# AugmentedStethoscope_v5a.net
KiCad netlist of a schematic drawn in EAGLE
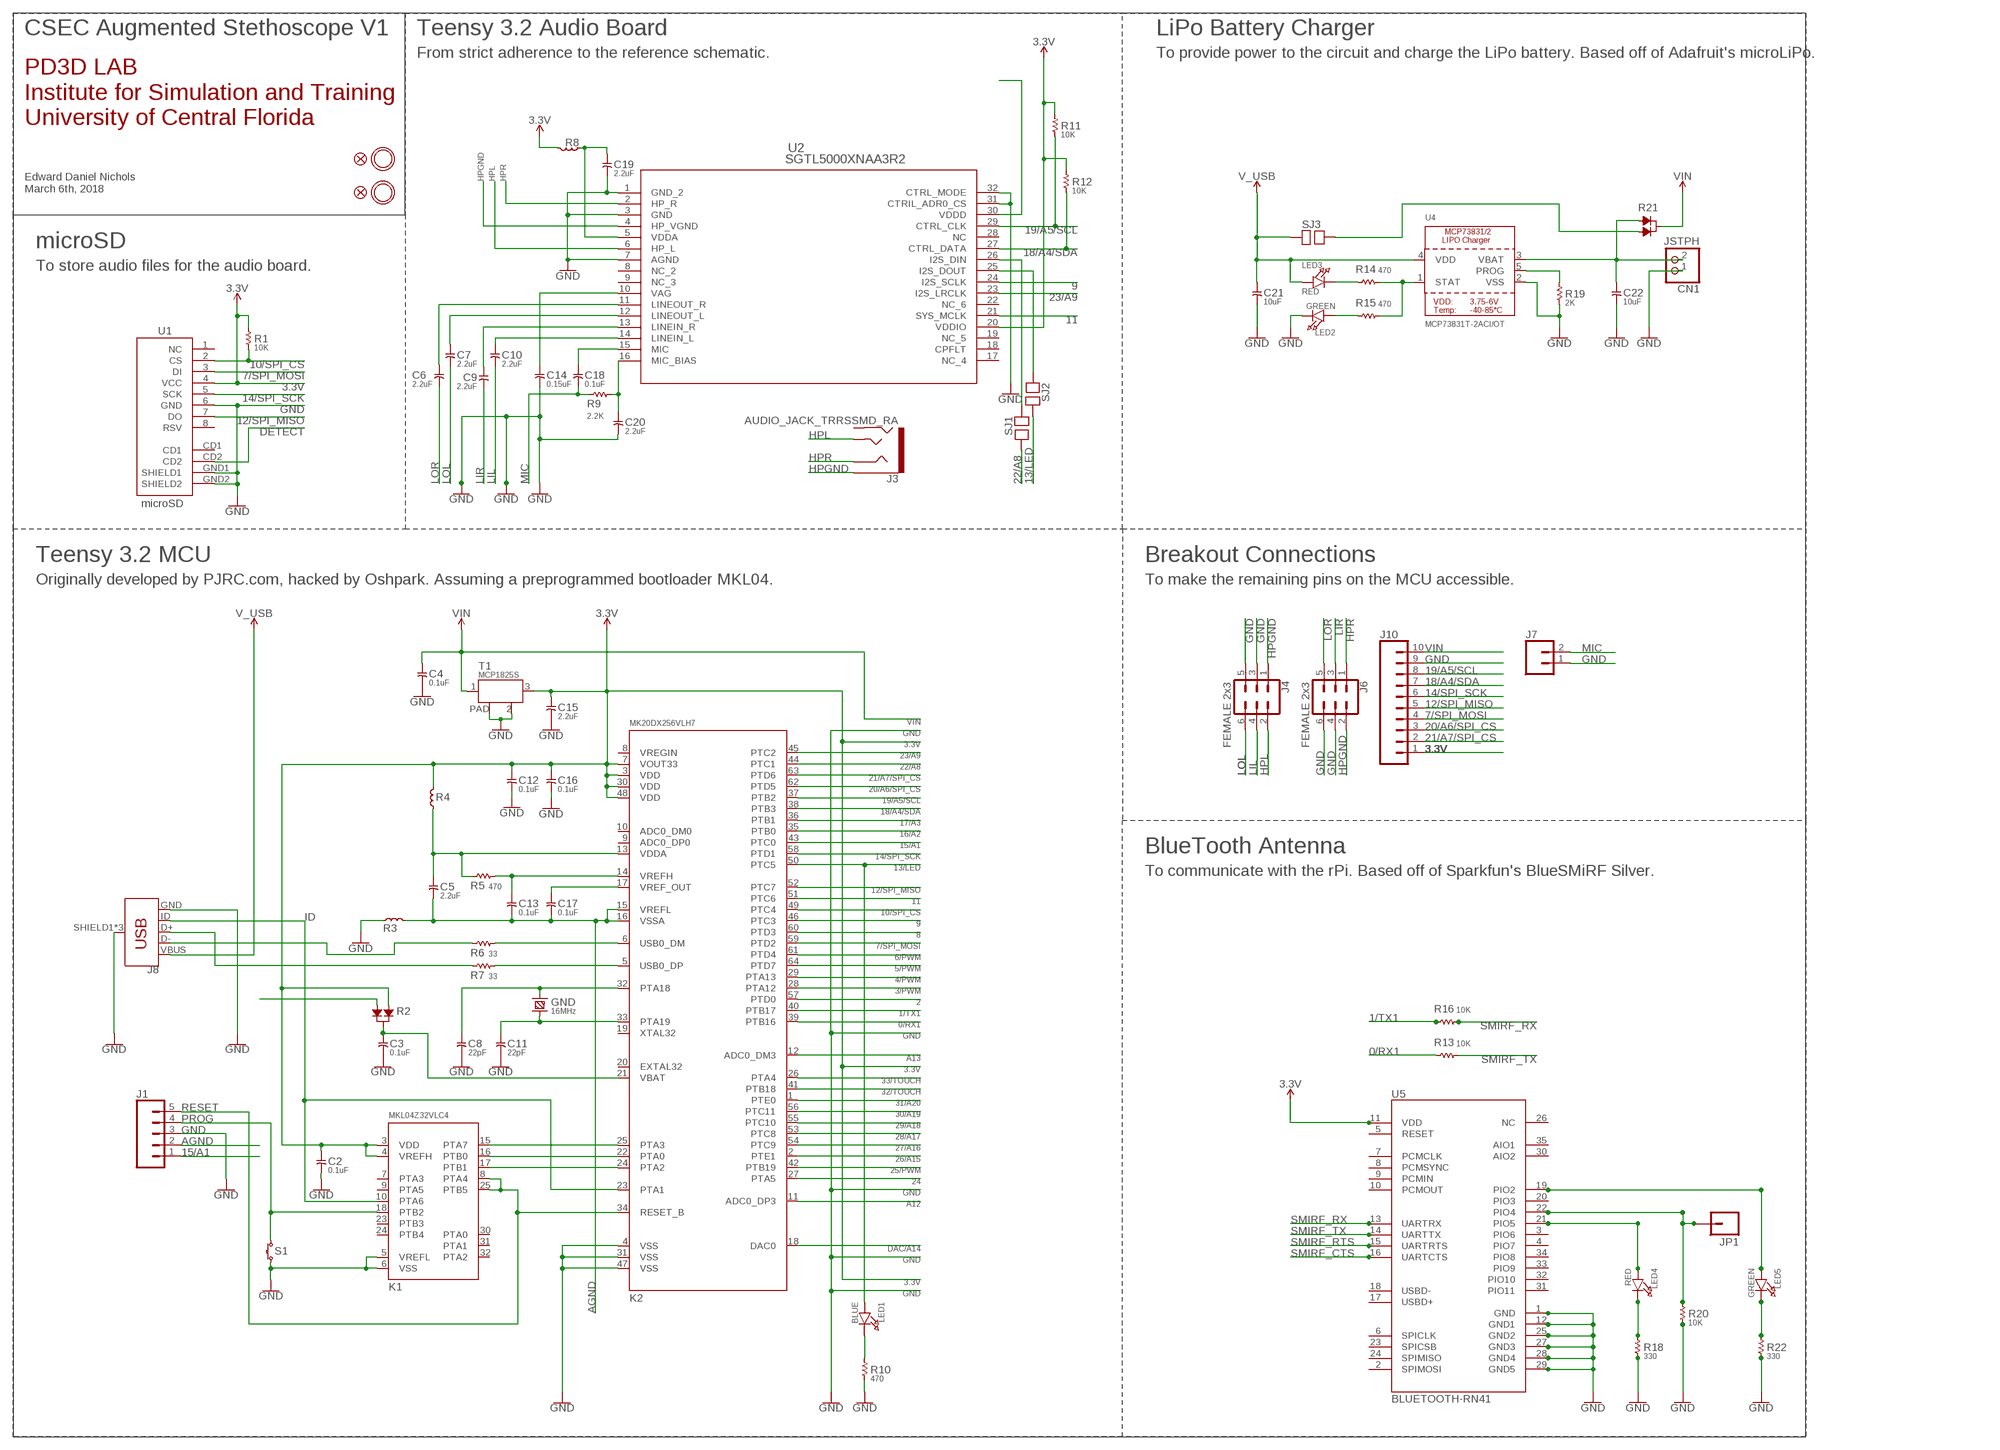
[diagram p0: schematic, sheet 1]

(export (version "E")
  (design (tool "Eeschema 10.0.6"))
  (components
    (comp (ref "C2")
      (value "0.1uF")
      (footprint "eagle-import:C0603")
      (fields (field (name "MF") "Murata Electronics") (field (name "MPN") "GRM188R71C104KA01D"))
      (libsource (lib "eagle-import") (part "CAPACITOR-0.1UF"))
    )
    (comp (ref "C3")
      (value "0.1uF")
      (footprint "eagle-import:C0603")
      (fields (field (name "MF") "Murata Electronics") (field (name "MPN") "GRM188R71C104KA01D"))
      (libsource (lib "eagle-import") (part "CAPACITOR-0.1UF"))
    )
    (comp (ref "C4")
      (value "0.1uF")
      (footprint "eagle-import:C0603")
      (fields (field (name "MF") "Murata Electronics") (field (name "MPN") "GRM188R71C104KA01D"))
      (libsource (lib "eagle-import") (part "CAPACITOR-0.1UF"))
    )
    (comp (ref "C5")
      (value "2.2uF")
      (footprint "eagle-import:C0805")
      (fields (field (name "MF") "Taiyo Yuden") (field (name "MPN") "TMK212B7225KG-TR"))
      (libsource (lib "eagle-import") (part "CAPACITOR-2.2UF"))
    )
    (comp (ref "C6")
      (value "2.2uF")
      (footprint "eagle-import:C0805")
      (fields (field (name "MF") "Taiyo Yuden") (field (name "MPN") "TMK212B7225KG-TR"))
      (libsource (lib "eagle-import") (part "CAPACITOR-2.2UF"))
    )
    (comp (ref "C7")
      (value "2.2uF")
      (footprint "eagle-import:C0805")
      (fields (field (name "MF") "Taiyo Yuden") (field (name "MPN") "TMK212B7225KG-TR"))
      (libsource (lib "eagle-import") (part "CAPACITOR-2.2UF"))
    )
    (comp (ref "C8")
      (value "22pF")
      (footprint "eagle-import:C0603")
      (fields (field (name "MF") "Vishay / Vitramon") (field (name "MPN") "VJ0603A220JXACW1BC"))
      (libsource (lib "eagle-import") (part "CAPACITOR-22PF"))
    )
    (comp (ref "C9")
      (value "2.2uF")
      (footprint "eagle-import:C0805")
      (fields (field (name "MF") "Taiyo Yuden") (field (name "MPN") "TMK212B7225KG-TR"))
      (libsource (lib "eagle-import") (part "CAPACITOR-2.2UF"))
    )
    (comp (ref "C10")
      (value "2.2uF")
      (footprint "eagle-import:C0805")
      (fields (field (name "MF") "Taiyo Yuden") (field (name "MPN") "TMK212B7225KG-TR"))
      (libsource (lib "eagle-import") (part "CAPACITOR-2.2UF"))
    )
    (comp (ref "C11")
      (value "22pF")
      (footprint "eagle-import:C0603")
      (fields (field (name "MF") "Vishay / Vitramon") (field (name "MPN") "VJ0603A220JXACW1BC"))
      (libsource (lib "eagle-import") (part "CAPACITOR-22PF"))
    )
    (comp (ref "C12")
      (value "0.1uF")
      (footprint "eagle-import:C0603")
      (fields (field (name "MF") "Murata Electronics") (field (name "MPN") "GRM188R71C104KA01D"))
      (libsource (lib "eagle-import") (part "CAPACITOR-0.1UF"))
    )
    (comp (ref "C13")
      (value "0.1uF")
      (footprint "eagle-import:C0603")
      (fields (field (name "MF") "Murata Electronics") (field (name "MPN") "GRM188R71C104KA01D"))
      (libsource (lib "eagle-import") (part "CAPACITOR-0.1UF"))
    )
    (comp (ref "C14")
      (value "0.15uF")
      (footprint "eagle-import:C0805")
      (fields (field (name "MF") "Taiyo Yuden") (field (name "MPN") "TMK212B7225KG-TR"))
      (libsource (lib "eagle-import") (part "CAPACITOR-2.2UF"))
    )
    (comp (ref "C15")
      (value "2.2uF")
      (footprint "eagle-import:C0805")
      (fields (field (name "MF") "Taiyo Yuden") (field (name "MPN") "TMK212B7225KG-TR"))
      (libsource (lib "eagle-import") (part "CAPACITOR-2.2UF"))
    )
    (comp (ref "C16")
      (value "0.1uF")
      (footprint "eagle-import:C0603")
      (fields (field (name "MF") "Murata Electronics") (field (name "MPN") "GRM188R71C104KA01D"))
      (libsource (lib "eagle-import") (part "CAPACITOR-0.1UF"))
    )
    (comp (ref "C17")
      (value "0.1uF")
      (footprint "eagle-import:C0603")
      (fields (field (name "MF") "Murata Electronics") (field (name "MPN") "GRM188R71C104KA01D"))
      (libsource (lib "eagle-import") (part "CAPACITOR-0.1UF"))
    )
    (comp (ref "C18")
      (value "0.1uF")
      (footprint "eagle-import:C0805")
      (fields (field (name "MF") "Taiyo Yuden") (field (name "MPN") "TMK212B7225KG-TR"))
      (libsource (lib "eagle-import") (part "CAPACITOR-2.2UF"))
    )
    (comp (ref "C19")
      (value "2.2uF")
      (footprint "eagle-import:C0805")
      (fields (field (name "MF") "Taiyo Yuden") (field (name "MPN") "TMK212B7225KG-TR"))
      (libsource (lib "eagle-import") (part "CAPACITOR-2.2UF"))
    )
    (comp (ref "C20")
      (value "2.2uF")
      (footprint "eagle-import:C0805")
      (fields (field (name "MF") "Taiyo Yuden") (field (name "MPN") "TMK212B7225KG-TR"))
      (libsource (lib "eagle-import") (part "CAPACITOR-2.2UF"))
    )
    (comp (ref "C21")
      (value "10uF")
      (footprint "eagle-import:C0603")
      (fields (field (name "MF") "Murata Electronics") (field (name "MPN") "GRM188R71C104KA01D"))
      (libsource (lib "eagle-import") (part "CAPACITOR-0.1UF"))
    )
    (comp (ref "C22")
      (value "10uF")
      (footprint "eagle-import:C0603")
      (fields (field (name "MF") "Murata Electronics") (field (name "MPN") "GRM188R71C104KA01D"))
      (libsource (lib "eagle-import") (part "CAPACITOR-0.1UF"))
    )
    (comp (ref "CN1")
      (value "JSTPH")
      (footprint "eagle-import:JSTPH2")
      (libsource (lib "eagle-import") (part "JST_2PIN"))
    )
    (comp (ref "FID2")
      (value "FIDUCIAL\"\"")
      (footprint "eagle-import:FIDUCIAL_1MM")
      (libsource (lib "eagle-import") (part "FIDUCIAL{dblquote}{dblquote}"))
    )
    (comp (ref "FID3")
      (value "FIDUCIAL\"\"")
      (footprint "eagle-import:FIDUCIAL_1MM")
      (fields (field (name "BOM") "EXCLUDE"))
      (libsource (lib "eagle-import") (part "FIDUCIAL{dblquote}{dblquote}"))
    )
    (comp (ref "GND")
      (value "16MHz")
      (footprint "eagle-import:HC49US")
      (fields (field (name "MF") "ABRACON") (field (name "MPN") "ABL-16.000MHz-B1U"))
      (libsource (lib "eagle-import") (part "CRYSTAL-HC49US"))
    )
    (comp (ref "J1")
      (value "CONN_05")
      (footprint "eagle-import:1X05")
      (libsource (lib "eagle-import") (part "CONN_05"))
    )
    (comp (ref "J3")
      (value "AUDIO_JACK_TRRSSMD_RA")
      (footprint "eagle-import:AUDIO_JACK_3.5MM_TRRS_SMD_RA")
      (libsource (lib "eagle-import") (part "AUDIO_JACK_TRRSSMD_RA"))
    )
    (comp (ref "J4")
      (value "FEMALE 2x3")
      (footprint "eagle-import:2X3")
      (libsource (lib "eagle-import") (part "CONN_03X2FEMALE"))
    )
    (comp (ref "J6")
      (value "FEMALE 2x3")
      (footprint "eagle-import:2X3")
      (libsource (lib "eagle-import") (part "CONN_03X2FEMALE"))
    )
    (comp (ref "J7")
      (value "CONN_02")
      (footprint "eagle-import:1X02")
      (libsource (lib "eagle-import") (part "CONN_02"))
    )
    (comp (ref "J8")
      (value "USB_MICRO-B_FEMALE-SMT")
      (footprint "eagle-import:USB-B-MICRO-SMD")
      (libsource (lib "eagle-import") (part "USB_MICRO-B_FEMALE-SMT"))
    )
    (comp (ref "J10")
      (value "CONN_10\"")
      (footprint "eagle-import:1X10")
      (libsource (lib "eagle-import") (part "CONN_10{dblquote}"))
    )
    (comp (ref "JP1")
      (value "M01SMDNS")
      (footprint "eagle-import:1X01NS")
      (libsource (lib "eagle-import") (part "M01SMDNS"))
    )
    (comp (ref "K1")
      (value "MKL04Z32VLC4")
      (footprint "eagle-import:LQFP32-08")
      (fields (field (name "MF") "PJRC") (field (name "MPN") "IC_MKL04Z32_TQFP32"))
      (libsource (lib "eagle-import") (part "MKL04Z32VLC4"))
    )
    (comp (ref "K2")
      (value "MK20DX256VLH7")
      (footprint "eagle-import:LQFP64-05")
      (fields (field (name "MF") "NXP"))
      (libsource (lib "eagle-import") (part "MK20DX256VLH7"))
    )
    (comp (ref "LED1")
      (value "BLUE")
      (footprint "eagle-import:CHIPLED_0805")
      (libsource (lib "eagle-import") (part "LED0805"))
    )
    (comp (ref "LED2")
      (value "GREEN")
      (footprint "eagle-import:CHIPLED_0805")
      (libsource (lib "eagle-import") (part "LED0805"))
    )
    (comp (ref "LED3")
      (value "RED")
      (footprint "eagle-import:CHIPLED_0805")
      (libsource (lib "eagle-import") (part "LED0805"))
    )
    (comp (ref "LED4")
      (value "RED")
      (footprint "eagle-import:CHIPLED_0805")
      (libsource (lib "eagle-import") (part "LED0805"))
    )
    (comp (ref "LED5")
      (value "GREEN")
      (footprint "eagle-import:CHIPLED_0805")
      (libsource (lib "eagle-import") (part "LED0805"))
    )
    (comp (ref "R1")
      (value "10K")
      (footprint "eagle-import:R0603")
      (fields (field (name "MF") "Vishay") (field (name "MPN") "CRCW0603470RFKEA"))
      (libsource (lib "eagle-import") (part "RESISTOR-470R"))
    )
    (comp (ref "R2")
      (value "DIODE_DUAL")
      (footprint "eagle-import:SOT-23")
      (fields (field (name "MF") "NXP Semiconductors") (field (name "MPN") "BAT54C,215"))
      (libsource (lib "eagle-import") (part "DIODE_DUAL"))
    )
    (comp (ref "R3")
      (value "FERRITE")
      (footprint "eagle-import:L0603")
      (fields (field (name "MF") "Murata Electronics") (field (name "MPN") " BLM18AG601SN1D"))
      (libsource (lib "eagle-import") (part "FERRITE"))
    )
    (comp (ref "R4")
      (value "FERRITE")
      (footprint "eagle-import:L0603")
      (fields (field (name "MF") "Murata Electronics") (field (name "MPN") " BLM18AG601SN1D"))
      (libsource (lib "eagle-import") (part "FERRITE"))
    )
    (comp (ref "R5")
      (value "470")
      (footprint "eagle-import:R0603")
      (fields (field (name "MF") "Vishay") (field (name "MPN") "CRCW0603470RFKEA"))
      (libsource (lib "eagle-import") (part "RESISTOR-470R"))
    )
    (comp (ref "R6")
      (value "33")
      (footprint "eagle-import:R0603")
      (fields (field (name "MF") "Panasonic") (field (name "MPN") "ERJ-PA3F33R0V"))
      (libsource (lib "eagle-import") (part "RESISTOR-33R"))
    )
    (comp (ref "R7")
      (value "33")
      (footprint "eagle-import:R0603")
      (fields (field (name "MF") "Panasonic") (field (name "MPN") "ERJ-PA3F33R0V"))
      (libsource (lib "eagle-import") (part "RESISTOR-33R"))
    )
    (comp (ref "R8")
      (value "FERRITE")
      (footprint "eagle-import:L0603")
      (fields (field (name "MF") "Murata Electronics") (field (name "MPN") " BLM18AG601SN1D"))
      (libsource (lib "eagle-import") (part "FERRITE"))
    )
    (comp (ref "R9")
      (value "2.2K")
      (footprint "eagle-import:R0603")
      (fields (field (name "MF") "Vishay") (field (name "MPN") "CRCW0603470RFKEA"))
      (libsource (lib "eagle-import") (part "RESISTOR-470R"))
    )
    (comp (ref "R10")
      (value "470")
      (footprint "eagle-import:R0603")
      (fields (field (name "MF") "Vishay") (field (name "MPN") "CRCW0603470RFKEA"))
      (libsource (lib "eagle-import") (part "RESISTOR-470R"))
    )
    (comp (ref "R11")
      (value "10K")
      (footprint "eagle-import:R0603")
      (fields (field (name "MF") "Vishay") (field (name "MPN") "CRCW0603470RFKEA"))
      (libsource (lib "eagle-import") (part "RESISTOR-470R"))
    )
    (comp (ref "R12")
      (value "10K")
      (footprint "eagle-import:R0603")
      (fields (field (name "MF") "Vishay") (field (name "MPN") "CRCW0603470RFKEA"))
      (libsource (lib "eagle-import") (part "RESISTOR-470R"))
    )
    (comp (ref "R13")
      (value "10K")
      (footprint "eagle-import:R0603")
      (fields (field (name "MF") "Panasonic") (field (name "MPN") "ERJ-PA3F33R0V"))
      (libsource (lib "eagle-import") (part "RESISTOR-33R"))
    )
    (comp (ref "R14")
      (value "470")
      (footprint "eagle-import:R0603")
      (fields (field (name "MF") "Panasonic") (field (name "MPN") "ERJ-PA3F33R0V"))
      (libsource (lib "eagle-import") (part "RESISTOR-33R"))
    )
    (comp (ref "R15")
      (value "470")
      (footprint "eagle-import:R0603")
      (fields (field (name "MF") "Panasonic") (field (name "MPN") "ERJ-PA3F33R0V"))
      (libsource (lib "eagle-import") (part "RESISTOR-33R"))
    )
    (comp (ref "R16")
      (value "10K")
      (footprint "eagle-import:R0603")
      (fields (field (name "MF") "Panasonic") (field (name "MPN") "ERJ-PA3F33R0V"))
      (libsource (lib "eagle-import") (part "RESISTOR-33R"))
    )
    (comp (ref "R18")
      (value "330")
      (footprint "eagle-import:R0603")
      (fields (field (name "MF") "Vishay") (field (name "MPN") "CRCW0603470RFKEA"))
      (libsource (lib "eagle-import") (part "RESISTOR-470R"))
    )
    (comp (ref "R19")
      (value "2K")
      (footprint "eagle-import:R0603")
      (fields (field (name "MF") "Vishay") (field (name "MPN") "CRCW0603470RFKEA"))
      (libsource (lib "eagle-import") (part "RESISTOR-470R"))
    )
    (comp (ref "R20")
      (value "10K")
      (footprint "eagle-import:R0603")
      (fields (field (name "MF") "Vishay") (field (name "MPN") "CRCW0603470RFKEA"))
      (libsource (lib "eagle-import") (part "RESISTOR-470R"))
    )
    (comp (ref "R21")
      (value "DIODE_DUAL")
      (footprint "eagle-import:SOT-23")
      (fields (field (name "MF") "NXP Semiconductors") (field (name "MPN") "BAT54C,215"))
      (libsource (lib "eagle-import") (part "DIODE_DUAL"))
    )
    (comp (ref "R22")
      (value "330")
      (footprint "eagle-import:R0603")
      (fields (field (name "MF") "Vishay") (field (name "MPN") "CRCW0603470RFKEA"))
      (libsource (lib "eagle-import") (part "RESISTOR-470R"))
    )
    (comp (ref "S1")
      (value "TACT_SWITCH")
      (footprint "eagle-import:ALPS_SKHH")
      (fields (field (name "MF") "ALPS") (field (name "MPN") "SKHHPKA010"))
      (libsource (lib "eagle-import") (part "TACT_SWITCH"))
    )
    (comp (ref "SJ1")
      (value "SOLDERJUMPER")
      (footprint "eagle-import:SOLDERJUMPER")
      (libsource (lib "eagle-import") (part "SOLDERJUMPER"))
    )
    (comp (ref "SJ2")
      (value "SOLDERJUMPER")
      (footprint "eagle-import:SOLDERJUMPER")
      (libsource (lib "eagle-import") (part "SOLDERJUMPER"))
    )
    (comp (ref "SJ3")
      (value "SOLDERJUMPER")
      (footprint "eagle-import:SOLDERJUMPER")
      (libsource (lib "eagle-import") (part "SOLDERJUMPER"))
    )
    (comp (ref "T1")
      (value "MCP1825S")
      (footprint "eagle-import:SOT-223")
      (fields (field (name "MF") "Microchip Technology") (field (name "MPN") "MCP1825S-3302E/DB"))
      (libsource (lib "eagle-import") (part "LDO"))
    )
    (comp (ref "U$1")
      (value "MOUNTINGHOLE2.5")
      (footprint "eagle-import:MOUNTINGHOLE_2.5_PLATED")
      (libsource (lib "eagle-import") (part "MOUNTINGHOLE2.5"))
    )
    (comp (ref "U$15")
      (value "MOUNTINGHOLE2.5")
      (footprint "eagle-import:MOUNTINGHOLE_2.5_PLATED")
      (libsource (lib "eagle-import") (part "MOUNTINGHOLE2.5"))
    )
    (comp (ref "U1")
      (value "microSD")
      (footprint "eagle-import:MICRO-SD-SOCKET-PP")
      (libsource (lib "eagle-import") (part "USD-SOCKETSMD"))
    )
    (comp (ref "U2")
      (value "SGTL5000XNAA3R2")
      (footprint "eagle-import:QFN32")
      (libsource (lib "eagle-import") (part "SGTL5000XNAA3R2"))
    )
    (comp (ref "U4")
      (value "MCP73831T-2ACI/OT")
      (footprint "eagle-import:SOT23-5")
      (libsource (lib "eagle-import") (part "MCP73831/2"))
    )
    (comp (ref "U5")
      (value "BLUETOOTH-RN41")
      (footprint "eagle-import:RN41")
      (libsource (lib "eagle-import") (part "BLUETOOTH-RN41{dblquote}"))
    )
  )
  (nets
    (net (code "1") (name "/0{slash}RX1") (class "Default")
      (node (ref "K2") (pin "39") (pinfunction "PTB16_39") (pintype "bidirectional"))
      (node (ref "R13") (pin "1") (pinfunction "1_1") (pintype "passive"))
    )
    (net (code "2") (name "/1{slash}TX1") (class "Default")
      (node (ref "K2") (pin "40") (pinfunction "PTB17_40") (pintype "bidirectional"))
      (node (ref "R16") (pin "1") (pinfunction "1_1") (pintype "passive"))
    )
    (net (code "3") (name "/2") (class "Default")
      (node (ref "K2") (pin "57") (pinfunction "PTD0_57") (pintype "bidirectional"))
    )
    (net (code "4") (name "/3{slash}PWM") (class "Default")
      (node (ref "K2") (pin "28") (pinfunction "PTA12_28") (pintype "bidirectional"))
    )
    (net (code "5") (name "/4{slash}PWM") (class "Default")
      (node (ref "K2") (pin "29") (pinfunction "PTA13_29") (pintype "bidirectional"))
    )
    (net (code "6") (name "/5{slash}PWM") (class "Default")
      (node (ref "K2") (pin "64") (pinfunction "PTD7_64") (pintype "bidirectional"))
    )
    (net (code "7") (name "/6{slash}PWM") (class "Default")
      (node (ref "K2") (pin "61") (pinfunction "PTD4_61") (pintype "bidirectional"))
    )
    (net (code "8") (name "/7{slash}SPI_MOSI") (class "Default")
      (node (ref "J10") (pin "4") (pinfunction "4_4") (pintype "passive"))
      (node (ref "K2") (pin "59") (pinfunction "PTD2_59") (pintype "bidirectional"))
      (node (ref "U1") (pin "3") (pinfunction "DI_3") (pintype "bidirectional"))
    )
    (net (code "9") (name "/8") (class "Default")
      (node (ref "K2") (pin "60") (pinfunction "PTD3_60") (pintype "bidirectional"))
    )
    (net (code "10") (name "/9") (class "Default")
      (node (ref "K2") (pin "46") (pinfunction "PTC3_46") (pintype "bidirectional"))
      (node (ref "U2") (pin "24") (pinfunction "I2S_SCLK_24") (pintype "passive"))
    )
    (net (code "11") (name "/10{slash}SPI_CS") (class "Default")
      (node (ref "K2") (pin "49") (pinfunction "PTC4_49") (pintype "bidirectional"))
      (node (ref "R1") (pin "1") (pinfunction "1_1") (pintype "passive"))
      (node (ref "U1") (pin "2") (pinfunction "CS_2") (pintype "bidirectional"))
    )
    (net (code "12") (name "/11") (class "Default")
      (node (ref "K2") (pin "51") (pinfunction "PTC6_51") (pintype "bidirectional"))
      (node (ref "U2") (pin "21") (pinfunction "SYS_MCLK_21") (pintype "passive"))
    )
    (net (code "13") (name "/12{slash}SPI_MISO") (class "Default")
      (node (ref "J10") (pin "5") (pinfunction "5_5") (pintype "passive"))
      (node (ref "K2") (pin "52") (pinfunction "PTC7_52") (pintype "bidirectional"))
      (node (ref "U1") (pin "7") (pinfunction "DO_7") (pintype "bidirectional"))
    )
    (net (code "14") (name "/13{slash}LED") (class "Default")
      (node (ref "K2") (pin "50") (pinfunction "PTC5_50") (pintype "bidirectional"))
      (node (ref "LED1") (pin "A") (pinfunction "A_A") (pintype "passive"))
      (node (ref "SJ2") (pin "2") (pinfunction "2_2") (pintype "passive"))
    )
    (net (code "15") (name "/14{slash}SPI_SCK") (class "Default")
      (node (ref "J10") (pin "6") (pinfunction "6_6") (pintype "passive"))
      (node (ref "K2") (pin "58") (pinfunction "PTD1_58") (pintype "bidirectional"))
      (node (ref "U1") (pin "5") (pinfunction "SCK_5") (pintype "bidirectional"))
    )
    (net (code "16") (name "/15{slash}A1") (class "Default")
      (node (ref "J1") (pin "1") (pinfunction "1_1") (pintype "passive"))
      (node (ref "K2") (pin "43") (pinfunction "PTC0_43") (pintype "bidirectional"))
    )
    (net (code "17") (name "/16{slash}A2") (class "Default")
      (node (ref "K2") (pin "35") (pinfunction "PTB0_35") (pintype "bidirectional"))
    )
    (net (code "18") (name "/17{slash}A3") (class "Default")
      (node (ref "K2") (pin "36") (pinfunction "PTB1_36") (pintype "bidirectional"))
    )
    (net (code "19") (name "/18{slash}A4{slash}SDA") (class "Default")
      (node (ref "J10") (pin "7") (pinfunction "7_7") (pintype "passive"))
      (node (ref "K2") (pin "38") (pinfunction "PTB3_38") (pintype "bidirectional"))
      (node (ref "R12") (pin "1") (pinfunction "1_1") (pintype "passive"))
      (node (ref "U2") (pin "27") (pinfunction "CTRL_DATA_27") (pintype "passive"))
    )
    (net (code "20") (name "/19{slash}A5{slash}SCL") (class "Default")
      (node (ref "J10") (pin "8") (pinfunction "8_8") (pintype "passive"))
      (node (ref "K2") (pin "37") (pinfunction "PTB2_37") (pintype "bidirectional"))
      (node (ref "R11") (pin "1") (pinfunction "1_1") (pintype "passive"))
      (node (ref "U2") (pin "29") (pinfunction "CTRL_CLK_29") (pintype "passive"))
    )
    (net (code "21") (name "/20{slash}A6{slash}SPI_CS") (class "Default")
      (node (ref "J10") (pin "3") (pinfunction "3_3") (pintype "passive"))
      (node (ref "K2") (pin "62") (pinfunction "PTD5_62") (pintype "bidirectional"))
    )
    (net (code "22") (name "/21{slash}A7{slash}SPI_CS") (class "Default")
      (node (ref "J10") (pin "2") (pinfunction "2_2") (pintype "passive"))
      (node (ref "K2") (pin "63") (pinfunction "PTD6_63") (pintype "bidirectional"))
    )
    (net (code "23") (name "/22{slash}A8") (class "Default")
      (node (ref "K2") (pin "44") (pinfunction "PTC1_44") (pintype "bidirectional"))
      (node (ref "SJ1") (pin "2") (pinfunction "2_2") (pintype "passive"))
    )
    (net (code "24") (name "/23{slash}A9") (class "Default")
      (node (ref "K2") (pin "45") (pinfunction "PTC2_45") (pintype "bidirectional"))
      (node (ref "U2") (pin "23") (pinfunction "I2S_LRCLK_23") (pintype "passive"))
    )
    (net (code "25") (name "/24") (class "Default")
      (node (ref "K2") (pin "27") (pinfunction "PTA5_27") (pintype "bidirectional"))
    )
    (net (code "26") (name "/25{slash}PWM") (class "Default")
      (node (ref "K2") (pin "42") (pinfunction "PTB19_42") (pintype "bidirectional"))
    )
    (net (code "27") (name "/26{slash}A15") (class "Default")
      (node (ref "K2") (pin "2") (pinfunction "PTE1_2") (pintype "bidirectional"))
    )
    (net (code "28") (name "/27{slash}A16") (class "Default")
      (node (ref "K2") (pin "54") (pinfunction "PTC9_54") (pintype "bidirectional"))
    )
    (net (code "29") (name "/28{slash}A17") (class "Default")
      (node (ref "K2") (pin "53") (pinfunction "PTC8_53") (pintype "bidirectional"))
    )
    (net (code "30") (name "/29{slash}A18") (class "Default")
      (node (ref "K2") (pin "55") (pinfunction "PTC10_55") (pintype "bidirectional"))
    )
    (net (code "31") (name "/30{slash}A19") (class "Default")
      (node (ref "K2") (pin "56") (pinfunction "PTC11_56") (pintype "bidirectional"))
    )
    (net (code "32") (name "/31{slash}A20") (class "Default")
      (node (ref "K2") (pin "1") (pinfunction "PTE0_1") (pintype "bidirectional"))
    )
    (net (code "33") (name "/32{slash}TOUCH") (class "Default")
      (node (ref "K2") (pin "41") (pinfunction "PTB18_41") (pintype "bidirectional"))
    )
    (net (code "34") (name "/33{slash}TOUCH") (class "Default")
      (node (ref "K2") (pin "26") (pinfunction "PTA4_26") (pintype "bidirectional"))
    )
    (net (code "35") (name "/A12") (class "Default")
      (node (ref "K2") (pin "11") (pinfunction "ADC0_DP3_11") (pintype "bidirectional"))
    )
    (net (code "36") (name "/A13") (class "Default")
      (node (ref "K2") (pin "12") (pinfunction "ADC0_DM3_12") (pintype "bidirectional"))
    )
    (net (code "37") (name "/AGND") (class "Default")
      (node (ref "C13") (pin "2") (pinfunction "2_2") (pintype "passive"))
      (node (ref "C17") (pin "2") (pinfunction "2_2") (pintype "passive"))
      (node (ref "C5") (pin "2") (pinfunction "2_2") (pintype "passive"))
      (node (ref "J1") (pin "2") (pinfunction "2_2") (pintype "passive"))
      (node (ref "K2") (pin "15") (pinfunction "VREFL_15") (pintype "bidirectional"))
      (node (ref "K2") (pin "16") (pinfunction "VSSA_16") (pintype "bidirectional"))
      (node (ref "R3") (pin "2") (pinfunction "2_2") (pintype "passive"))
    )
    (net (code "38") (name "/DAC{slash}A14") (class "Default")
      (node (ref "K2") (pin "18") (pinfunction "DAC0_18") (pintype "bidirectional"))
    )
    (net (code "39") (name "/DETECT") (class "Default")
      (node (ref "U1") (pin "CD2") (pinfunction "CD2_CD2") (pintype "bidirectional"))
    )
    (net (code "40") (name "/HPGND") (class "Default")
      (node (ref "J3") (pin "EARTH") (pinfunction "EARTH_EARTH") (pintype "bidirectional"))
      (node (ref "J4") (pin "1") (pinfunction "1_1") (pintype "bidirectional"))
      (node (ref "J6") (pin "2") (pinfunction "2_2") (pintype "bidirectional"))
      (node (ref "U2") (pin "4") (pinfunction "HP_VGND_4") (pintype "power_in"))
    )
    (net (code "41") (name "/HPL") (class "Default")
      (node (ref "J3") (pin "TIP") (pinfunction "TIP_TIP") (pintype "bidirectional"))
      (node (ref "J4") (pin "2") (pinfunction "2_2") (pintype "bidirectional"))
      (node (ref "U2") (pin "6") (pinfunction "HP_L_6") (pintype "output"))
    )
    (net (code "42") (name "/HPR") (class "Default")
      (node (ref "J3") (pin "RING1") (pinfunction "RING1_RING1") (pintype "bidirectional"))
      (node (ref "J6") (pin "1") (pinfunction "1_1") (pintype "bidirectional"))
      (node (ref "U2") (pin "2") (pinfunction "HP_R_2") (pintype "output"))
    )
    (net (code "43") (name "/ID") (class "Default")
      (node (ref "J8") (pin "ID") (pinfunction "ID_ID") (pintype "bidirectional"))
      (node (ref "K1") (pin "10") (pinfunction "PTA6_10") (pintype "bidirectional"))
      (node (ref "K2") (pin "23") (pinfunction "PTA1_23") (pintype "bidirectional"))
    )
    (net (code "44") (name "/LIL") (class "Default")
      (node (ref "C10") (pin "2") (pinfunction "2_2") (pintype "passive"))
      (node (ref "J4") (pin "4") (pinfunction "4_4") (pintype "bidirectional"))
    )
    (net (code "45") (name "/LIR") (class "Default")
      (node (ref "C9") (pin "2") (pinfunction "2_2") (pintype "passive"))
      (node (ref "J6") (pin "3") (pinfunction "3_3") (pintype "bidirectional"))
    )
    (net (code "46") (name "/LOL") (class "Default")
      (node (ref "C7") (pin "2") (pinfunction "2_2") (pintype "passive"))
      (node (ref "J4") (pin "6") (pinfunction "6_6") (pintype "bidirectional"))
    )
    (net (code "47") (name "/LOR") (class "Default")
      (node (ref "C6") (pin "2") (pinfunction "2_2") (pintype "passive"))
      (node (ref "J6") (pin "5") (pinfunction "5_5") (pintype "bidirectional"))
    )
    (net (code "48") (name "/MIC") (class "Default")
      (node (ref "C18") (pin "2") (pinfunction "2_2") (pintype "passive"))
      (node (ref "J7") (pin "2") (pinfunction "2_2") (pintype "passive"))
      (node (ref "R9") (pin "1") (pinfunction "1_1") (pintype "passive"))
    )
    (net (code "49") (name "/PROG") (class "Default")
      (node (ref "J1") (pin "4") (pinfunction "4_4") (pintype "passive"))
      (node (ref "K1") (pin "18") (pinfunction "PTB2_18") (pintype "bidirectional"))
      (node (ref "S1") (pin "1") (pinfunction "1_1") (pintype "passive"))
      (node (ref "S1") (pin "2") (pinfunction "1_2") (pintype "passive"))
    )
    (net (code "50") (name "/RESET") (class "Default")
      (node (ref "J1") (pin "5") (pinfunction "5_5") (pintype "passive"))
      (node (ref "K1") (pin "25") (pinfunction "PTB5_25") (pintype "bidirectional"))
      (node (ref "K1") (pin "8") (pinfunction "PTA4_8") (pintype "bidirectional"))
      (node (ref "K2") (pin "34") (pinfunction "RESET_B_34") (pintype "bidirectional"))
    )
    (net (code "51") (name "/SMIRF_CTS") (class "Default")
      (node (ref "U5") (pin "16") (pinfunction "UARTCTS_16") (pintype "bidirectional"))
    )
    (net (code "52") (name "/SMIRF_RTS") (class "Default")
      (node (ref "U5") (pin "15") (pinfunction "UARTRTS_15") (pintype "bidirectional"))
    )
    (net (code "53") (name "/SMIRF_RX") (class "Default")
      (node (ref "R16") (pin "2") (pinfunction "2_2") (pintype "passive"))
      (node (ref "U5") (pin "13") (pinfunction "UARTRX_13") (pintype "bidirectional"))
    )
    (net (code "54") (name "/SMIRF_TX") (class "Default")
      (node (ref "R13") (pin "2") (pinfunction "2_2") (pintype "passive"))
      (node (ref "U5") (pin "14") (pinfunction "UARTTX_14") (pintype "bidirectional"))
    )
    (net (code "55") (name "3.3V") (class "Default")
      (node (ref "C12") (pin "1") (pinfunction "1_1") (pintype "passive"))
      (node (ref "C15") (pin "1") (pinfunction "1_1") (pintype "passive"))
      (node (ref "C16") (pin "1") (pinfunction "1_1") (pintype "passive"))
      (node (ref "C2") (pin "1") (pinfunction "1_1") (pintype "passive"))
      (node (ref "J10") (pin "1") (pinfunction "1_1") (pintype "passive"))
      (node (ref "K1") (pin "3") (pinfunction "VDD_3") (pintype "bidirectional"))
      (node (ref "K1") (pin "4") (pinfunction "VREFH_4") (pintype "bidirectional"))
      (node (ref "K2") (pin "3") (pinfunction "VDD_3") (pintype "bidirectional"))
      (node (ref "K2") (pin "30") (pinfunction "VDD_30") (pintype "bidirectional"))
      (node (ref "K2") (pin "48") (pinfunction "VDD_48") (pintype "bidirectional"))
      (node (ref "K2") (pin "7") (pinfunction "VOUT33_7") (pintype "bidirectional"))
      (node (ref "R1") (pin "2") (pinfunction "2_2") (pintype "passive"))
      (node (ref "R11") (pin "2") (pinfunction "2_2") (pintype "passive"))
      (node (ref "R12") (pin "2") (pinfunction "2_2") (pintype "passive"))
      (node (ref "R2") (pin "1") (pinfunction "1_1") (pintype "bidirectional"))
      (node (ref "R4") (pin "2") (pinfunction "2_2") (pintype "passive"))
      (node (ref "R8") (pin "2") (pinfunction "2_2") (pintype "passive"))
      (node (ref "T1") (pin "3") (pinfunction "OUT_3") (pintype "bidirectional"))
      (node (ref "U1") (pin "4") (pinfunction "VCC_4") (pintype "bidirectional"))
      (node (ref "U2") (pin "20") (pinfunction "VDDIO_20") (pintype "power_in"))
      (node (ref "U5") (pin "11") (pinfunction "VDD_11") (pintype "bidirectional"))
    )
    (net (code "56") (name "GND") (class "Default")
      (node (ref "C11") (pin "2") (pinfunction "2_2") (pintype "passive"))
      (node (ref "C12") (pin "2") (pinfunction "2_2") (pintype "passive"))
      (node (ref "C14") (pin "2") (pinfunction "2_2") (pintype "passive"))
      (node (ref "C15") (pin "2") (pinfunction "2_2") (pintype "passive"))
      (node (ref "C16") (pin "2") (pinfunction "2_2") (pintype "passive"))
      (node (ref "C19") (pin "2") (pinfunction "2_2") (pintype "passive"))
      (node (ref "C2") (pin "2") (pinfunction "2_2") (pintype "passive"))
      (node (ref "C20") (pin "2") (pinfunction "2_2") (pintype "passive"))
      (node (ref "C21") (pin "2") (pinfunction "2_2") (pintype "passive"))
      (node (ref "C22") (pin "2") (pinfunction "2_2") (pintype "passive"))
      (node (ref "C3") (pin "2") (pinfunction "2_2") (pintype "passive"))
      (node (ref "C4") (pin "2") (pinfunction "2_2") (pintype "passive"))
      (node (ref "C8") (pin "2") (pinfunction "2_2") (pintype "passive"))
      (node (ref "CN1") (pin "1") (pinfunction "1_1") (pintype "passive"))
      (node (ref "J1") (pin "3") (pinfunction "3_3") (pintype "passive"))
      (node (ref "J10") (pin "9") (pinfunction "9_9") (pintype "passive"))
      (node (ref "J4") (pin "3") (pinfunction "3_3") (pintype "bidirectional"))
      (node (ref "J4") (pin "5") (pinfunction "5_5") (pintype "bidirectional"))
      (node (ref "J6") (pin "4") (pinfunction "4_4") (pintype "bidirectional"))
      (node (ref "J6") (pin "6") (pinfunction "6_6") (pintype "bidirectional"))
      (node (ref "J7") (pin "1") (pinfunction "1_1") (pintype "passive"))
      (node (ref "J8") (pin "GND") (pinfunction "GND_GND") (pintype "power_in"))
      (node (ref "J8") (pin "SHIELD1") (pinfunction "SHIELD_SHIELD1") (pintype "bidirectional"))
      (node (ref "J8") (pin "SHIELD2") (pinfunction "SHIELD_SHIELD2") (pintype "bidirectional"))
      (node (ref "J8") (pin "SHIELD3") (pinfunction "SHIELD_SHIELD3") (pintype "bidirectional"))
      (node (ref "K1") (pin "5") (pinfunction "VREFL_5") (pintype "bidirectional"))
      (node (ref "K1") (pin "6") (pinfunction "VSS_6") (pintype "bidirectional"))
      (node (ref "K2") (pin "31") (pinfunction "VSS_31") (pintype "bidirectional"))
      (node (ref "K2") (pin "4") (pinfunction "VSS_4") (pintype "bidirectional"))
      (node (ref "K2") (pin "47") (pinfunction "VSS_47") (pintype "bidirectional"))
      (node (ref "LED2") (pin "C") (pinfunction "C_C") (pintype "passive"))
      (node (ref "R10") (pin "1") (pinfunction "1_1") (pintype "passive"))
      (node (ref "R18") (pin "1") (pinfunction "1_1") (pintype "passive"))
      (node (ref "R19") (pin "1") (pinfunction "1_1") (pintype "passive"))
      (node (ref "R20") (pin "1") (pinfunction "1_1") (pintype "passive"))
      (node (ref "R22") (pin "1") (pinfunction "1_1") (pintype "passive"))
      (node (ref "R3") (pin "1") (pinfunction "1_1") (pintype "passive"))
      (node (ref "S1") (pin "3") (pinfunction "3_3") (pintype "passive"))
      (node (ref "S1") (pin "4") (pinfunction "3_4") (pintype "passive"))
      (node (ref "T1") (pin "2") (pinfunction "GND_2") (pintype "bidirectional"))
      (node (ref "T1") (pin "PAD") (pinfunction "PAD_PAD") (pintype "bidirectional"))
      (node (ref "U1") (pin "6") (pinfunction "GND_6") (pintype "bidirectional"))
      (node (ref "U1") (pin "GND1") (pinfunction "SHIELD1_GND1") (pintype "bidirectional"))
      (node (ref "U1") (pin "GND2") (pinfunction "SHIELD2_GND2") (pintype "bidirectional"))
      (node (ref "U2") (pin "1") (pinfunction "GND_2_1") (pintype "power_in"))
      (node (ref "U2") (pin "3") (pinfunction "GND_3") (pintype "power_in"))
      (node (ref "U2") (pin "31") (pinfunction "CTRIL_ADR0_CS_31") (pintype "passive"))
      (node (ref "U2") (pin "32") (pinfunction "CTRL_MODE_32") (pintype "passive"))
      (node (ref "U2") (pin "7") (pinfunction "AGND_7") (pintype "power_in"))
      (node (ref "U4") (pin "2") (pinfunction "VSS_2") (pintype "power_in"))
      (node (ref "U5") (pin "1") (pinfunction "GND_1") (pintype "bidirectional"))
      (node (ref "U5") (pin "12") (pinfunction "GND1_12") (pintype "bidirectional"))
      (node (ref "U5") (pin "25") (pinfunction "GND2_25") (pintype "bidirectional"))
      (node (ref "U5") (pin "27") (pinfunction "GND3_27") (pintype "bidirectional"))
      (node (ref "U5") (pin "28") (pinfunction "GND4_28") (pintype "bidirectional"))
      (node (ref "U5") (pin "29") (pinfunction "GND5_29") (pintype "bidirectional"))
    )
    (net (code "57") (name "Net-(J8-PadD+)") (class "Default")
      (node (ref "J8") (pin "D+") (pinfunction "D+_D+") (pintype "bidirectional"))
      (node (ref "R7") (pin "1") (pinfunction "1_1") (pintype "passive"))
    )
    (net (code "58") (name "Net-(J8-PadD-)") (class "Default")
      (node (ref "J8") (pin "D-") (pinfunction "D-_D-") (pintype "bidirectional"))
      (node (ref "R6") (pin "1") (pinfunction "1_1") (pintype "passive"))
    )
    (net (code "59") (name "Net-(K1-PTA7)") (class "Default")
      (node (ref "K1") (pin "15") (pinfunction "PTA7_15") (pintype "bidirectional"))
      (node (ref "K2") (pin "25") (pinfunction "PTA3_25") (pintype "bidirectional"))
    )
    (net (code "60") (name "Net-(K1-PTB0)") (class "Default")
      (node (ref "K1") (pin "16") (pinfunction "PTB0_16") (pintype "bidirectional"))
      (node (ref "K2") (pin "22") (pinfunction "PTA0_22") (pintype "bidirectional"))
    )
    (net (code "61") (name "Net-(K1-PTB1)") (class "Default")
      (node (ref "K1") (pin "17") (pinfunction "PTB1_17") (pintype "bidirectional"))
      (node (ref "K2") (pin "24") (pinfunction "PTA2_24") (pintype "bidirectional"))
    )
    (net (code "62") (name "Net-(K2-PTA18)") (class "Default")
      (node (ref "C8") (pin "1") (pinfunction "1_1") (pintype "passive"))
      (node (ref "GND") (pin "1") (pinfunction "1_1") (pintype "passive"))
      (node (ref "K2") (pin "32") (pinfunction "PTA18_32") (pintype "bidirectional"))
    )
    (net (code "63") (name "Net-(K2-PTA19)") (class "Default")
      (node (ref "C11") (pin "1") (pinfunction "1_1") (pintype "passive"))
      (node (ref "GND") (pin "2") (pinfunction "2_2") (pintype "passive"))
      (node (ref "K2") (pin "33") (pinfunction "PTA19_33") (pintype "bidirectional"))
    )
    (net (code "64") (name "Net-(K2-USB0_DM)") (class "Default")
      (node (ref "K2") (pin "6") (pinfunction "USB0_DM_6") (pintype "bidirectional"))
      (node (ref "R6") (pin "2") (pinfunction "2_2") (pintype "passive"))
    )
    (net (code "65") (name "Net-(K2-USB0_DP)") (class "Default")
      (node (ref "K2") (pin "5") (pinfunction "USB0_DP_5") (pintype "bidirectional"))
      (node (ref "R7") (pin "2") (pinfunction "2_2") (pintype "passive"))
    )
    (net (code "66") (name "Net-(K2-VBAT)") (class "Default")
      (node (ref "C3") (pin "1") (pinfunction "1_1") (pintype "passive"))
      (node (ref "K2") (pin "21") (pinfunction "VBAT_21") (pintype "bidirectional"))
      (node (ref "R2") (pin "3") (pinfunction "3_3") (pintype "bidirectional"))
    )
    (net (code "67") (name "Net-(K2-VDDA)") (class "Default")
      (node (ref "C5") (pin "1") (pinfunction "1_1") (pintype "passive"))
      (node (ref "K2") (pin "13") (pinfunction "VDDA_13") (pintype "bidirectional"))
      (node (ref "R4") (pin "1") (pinfunction "1_1") (pintype "passive"))
      (node (ref "R5") (pin "1") (pinfunction "1_1") (pintype "passive"))
    )
    (net (code "68") (name "Net-(K2-VREFH)") (class "Default")
      (node (ref "C13") (pin "1") (pinfunction "1_1") (pintype "passive"))
      (node (ref "K2") (pin "14") (pinfunction "VREFH_14") (pintype "bidirectional"))
      (node (ref "R5") (pin "2") (pinfunction "2_2") (pintype "passive"))
    )
    (net (code "69") (name "Net-(K2-VREF_OUT)") (class "Default")
      (node (ref "C17") (pin "1") (pinfunction "1_1") (pintype "passive"))
      (node (ref "K2") (pin "17") (pinfunction "VREF_OUT_17") (pintype "bidirectional"))
    )
    (net (code "70") (name "Net-(LED1-PadC)") (class "Default")
      (node (ref "LED1") (pin "C") (pinfunction "C_C") (pintype "passive"))
      (node (ref "R10") (pin "2") (pinfunction "2_2") (pintype "passive"))
    )
    (net (code "71") (name "Net-(LED2-PadA)") (class "Default")
      (node (ref "LED2") (pin "A") (pinfunction "A_A") (pintype "passive"))
      (node (ref "R15") (pin "1") (pinfunction "1_1") (pintype "passive"))
    )
    (net (code "72") (name "Net-(LED3-PadC)") (class "Default")
      (node (ref "LED3") (pin "C") (pinfunction "C_C") (pintype "passive"))
      (node (ref "R14") (pin "1") (pinfunction "1_1") (pintype "passive"))
    )
    (net (code "73") (name "Net-(LED4-PadC)") (class "Default")
      (node (ref "LED4") (pin "C") (pinfunction "C_C") (pintype "passive"))
      (node (ref "R18") (pin "2") (pinfunction "2_2") (pintype "passive"))
    )
    (net (code "74") (name "Net-(LED5-PadC)") (class "Default")
      (node (ref "LED5") (pin "C") (pinfunction "C_C") (pintype "passive"))
      (node (ref "R22") (pin "2") (pinfunction "2_2") (pintype "passive"))
    )
    (net (code "75") (name "Net-(R21-Pad2)") (class "Default")
      (node (ref "R21") (pin "2") (pinfunction "2_2") (pintype "bidirectional"))
      (node (ref "SJ3") (pin "2") (pinfunction "2_2") (pintype "passive"))
    )
    (net (code "76") (name "Net-(U2-I2S_DIN)") (class "Default")
      (node (ref "SJ1") (pin "1") (pinfunction "1_1") (pintype "passive"))
      (node (ref "U2") (pin "26") (pinfunction "I2S_DIN_26") (pintype "input"))
    )
    (net (code "77") (name "Net-(U2-I2S_DOUT)") (class "Default")
      (node (ref "SJ2") (pin "1") (pinfunction "1_1") (pintype "passive"))
      (node (ref "U2") (pin "25") (pinfunction "I2S_DOUT_25") (pintype "output"))
    )
    (net (code "78") (name "Net-(U2-LINEIN_L)") (class "Default")
      (node (ref "C10") (pin "1") (pinfunction "1_1") (pintype "passive"))
      (node (ref "U2") (pin "14") (pinfunction "LINEIN_L_14") (pintype "input"))
    )
    (net (code "79") (name "Net-(U2-LINEIN_R)") (class "Default")
      (node (ref "C9") (pin "1") (pinfunction "1_1") (pintype "passive"))
      (node (ref "U2") (pin "13") (pinfunction "LINEIN_R_13") (pintype "input"))
    )
    (net (code "80") (name "Net-(U2-LINEOUT_L)") (class "Default")
      (node (ref "C7") (pin "1") (pinfunction "1_1") (pintype "passive"))
      (node (ref "U2") (pin "12") (pinfunction "LINEOUT_L_12") (pintype "output"))
    )
    (net (code "81") (name "Net-(U2-LINEOUT_R)") (class "Default")
      (node (ref "C6") (pin "1") (pinfunction "1_1") (pintype "passive"))
      (node (ref "U2") (pin "11") (pinfunction "LINEOUT_R_11") (pintype "output"))
    )
    (net (code "82") (name "Net-(U2-MIC)") (class "Default")
      (node (ref "C18") (pin "1") (pinfunction "1_1") (pintype "passive"))
      (node (ref "U2") (pin "15") (pinfunction "MIC_15") (pintype "input"))
    )
    (net (code "83") (name "Net-(U2-MIC_BIAS)") (class "Default")
      (node (ref "C20") (pin "1") (pinfunction "1_1") (pintype "passive"))
      (node (ref "R9") (pin "2") (pinfunction "2_2") (pintype "passive"))
      (node (ref "U2") (pin "16") (pinfunction "MIC_BIAS_16") (pintype "passive"))
    )
    (net (code "84") (name "Net-(U2-VAG)") (class "Default")
      (node (ref "C14") (pin "1") (pinfunction "1_1") (pintype "passive"))
      (node (ref "U2") (pin "10") (pinfunction "VAG_10") (pintype "passive"))
    )
    (net (code "85") (name "Net-(U2-VDDA)") (class "Default")
      (node (ref "C19") (pin "1") (pinfunction "1_1") (pintype "passive"))
      (node (ref "R8") (pin "1") (pinfunction "1_1") (pintype "passive"))
      (node (ref "U2") (pin "5") (pinfunction "VDDA_5") (pintype "power_in"))
    )
    (net (code "86") (name "Net-(U4-PROG)") (class "Default")
      (node (ref "R19") (pin "2") (pinfunction "2_2") (pintype "passive"))
      (node (ref "U4") (pin "5") (pinfunction "PROG_5") (pintype "input"))
    )
    (net (code "87") (name "Net-(U4-STAT)") (class "Default")
      (node (ref "R14") (pin "2") (pinfunction "2_2") (pintype "passive"))
      (node (ref "R15") (pin "2") (pinfunction "2_2") (pintype "passive"))
      (node (ref "U4") (pin "1") (pinfunction "STAT_1") (pintype "output"))
    )
    (net (code "88") (name "Net-(U4-VBAT)") (class "Default")
      (node (ref "C22") (pin "1") (pinfunction "1_1") (pintype "passive"))
      (node (ref "CN1") (pin "2") (pinfunction "2_2") (pintype "passive"))
      (node (ref "R21") (pin "1") (pinfunction "1_1") (pintype "bidirectional"))
      (node (ref "U4") (pin "3") (pinfunction "VBAT_3") (pintype "power_in"))
    )
    (net (code "89") (name "Net-(U5-PIO2)") (class "Default")
      (node (ref "LED5") (pin "A") (pinfunction "A_A") (pintype "passive"))
      (node (ref "U5") (pin "19") (pinfunction "PIO2_19") (pintype "bidirectional"))
    )
    (net (code "90") (name "Net-(U5-PIO4)") (class "Default")
      (node (ref "JP1") (pin "1") (pinfunction "1_1") (pintype "passive"))
      (node (ref "R20") (pin "2") (pinfunction "2_2") (pintype "passive"))
      (node (ref "U5") (pin "22") (pinfunction "PIO4_22") (pintype "bidirectional"))
    )
    (net (code "91") (name "Net-(U5-PIO5)") (class "Default")
      (node (ref "LED4") (pin "A") (pinfunction "A_A") (pintype "passive"))
      (node (ref "U5") (pin "21") (pinfunction "PIO5_21") (pintype "bidirectional"))
    )
    (net (code "92") (name "VIN") (class "Default")
      (node (ref "C4") (pin "1") (pinfunction "1_1") (pintype "passive"))
      (node (ref "J10") (pin "10") (pinfunction "10_10") (pintype "passive"))
      (node (ref "R21") (pin "3") (pinfunction "3_3") (pintype "bidirectional"))
      (node (ref "T1") (pin "1") (pinfunction "IN_1") (pintype "bidirectional"))
    )
    (net (code "93") (name "V_USB") (class "Default")
      (node (ref "C21") (pin "1") (pinfunction "1_1") (pintype "passive"))
      (node (ref "J8") (pin "VBUS") (pinfunction "VBUS_VBUS") (pintype "power_in"))
      (node (ref "LED3") (pin "A") (pinfunction "A_A") (pintype "passive"))
      (node (ref "SJ3") (pin "1") (pinfunction "1_1") (pintype "passive"))
      (node (ref "U4") (pin "4") (pinfunction "VDD_4") (pintype "power_in"))
    )
    (net (code "94") (name "unconnected-(J3-PadRING2)") (class "Default")
      (node (ref "J3") (pin "RING2") (pinfunction "RING2_RING2") (pintype "bidirectional"))
    )
    (net (code "95") (name "unconnected-(K1-PTA0-Pad30)") (class "Default")
      (node (ref "K1") (pin "30") (pinfunction "PTA0_30") (pintype "bidirectional"))
    )
    (net (code "96") (name "unconnected-(K1-PTA1-Pad31)") (class "Default")
      (node (ref "K1") (pin "31") (pinfunction "PTA1_31") (pintype "bidirectional"))
    )
    (net (code "97") (name "unconnected-(K1-PTA2-Pad32)") (class "Default")
      (node (ref "K1") (pin "32") (pinfunction "PTA2_32") (pintype "bidirectional"))
    )
    (net (code "98") (name "unconnected-(K1-PTA3-Pad7)") (class "Default")
      (node (ref "K1") (pin "7") (pinfunction "PTA3_7") (pintype "bidirectional"))
    )
    (net (code "99") (name "unconnected-(K1-PTA5-Pad9)") (class "Default")
      (node (ref "K1") (pin "9") (pinfunction "PTA5_9") (pintype "bidirectional"))
    )
    (net (code "100") (name "unconnected-(K1-PTB3-Pad23)") (class "Default")
      (node (ref "K1") (pin "23") (pinfunction "PTB3_23") (pintype "bidirectional"))
    )
    (net (code "101") (name "unconnected-(K1-PTB4-Pad24)") (class "Default")
      (node (ref "K1") (pin "24") (pinfunction "PTB4_24") (pintype "bidirectional"))
    )
    (net (code "102") (name "unconnected-(K2-ADC0_DM0-Pad10)") (class "Default")
      (node (ref "K2") (pin "10") (pinfunction "ADC0_DM0_10") (pintype "bidirectional"))
    )
    (net (code "103") (name "unconnected-(K2-ADC0_DP0-Pad9)") (class "Default")
      (node (ref "K2") (pin "9") (pinfunction "ADC0_DP0_9") (pintype "bidirectional"))
    )
    (net (code "104") (name "unconnected-(K2-EXTAL32-Pad20)") (class "Default")
      (node (ref "K2") (pin "20") (pinfunction "EXTAL32_20") (pintype "bidirectional"))
    )
    (net (code "105") (name "unconnected-(K2-VREGIN-Pad8)") (class "Default")
      (node (ref "K2") (pin "8") (pinfunction "VREGIN_8") (pintype "bidirectional"))
    )
    (net (code "106") (name "unconnected-(K2-XTAL32-Pad19)") (class "Default")
      (node (ref "K2") (pin "19") (pinfunction "XTAL32_19") (pintype "bidirectional"))
    )
    (net (code "107") (name "unconnected-(R2-Pad2)") (class "Default")
      (node (ref "R2") (pin "2") (pinfunction "2_2") (pintype "bidirectional"))
    )
    (net (code "108") (name "unconnected-(U1-NC-Pad1)") (class "Default")
      (node (ref "U1") (pin "1") (pinfunction "NC_1") (pintype "bidirectional"))
    )
    (net (code "109") (name "unconnected-(U1-PadCD1)") (class "Default")
      (node (ref "U1") (pin "CD1") (pinfunction "CD1_CD1") (pintype "bidirectional"))
    )
    (net (code "110") (name "unconnected-(U1-RSV-Pad8)") (class "Default")
      (node (ref "U1") (pin "8") (pinfunction "RSV_8") (pintype "bidirectional"))
    )
    (net (code "111") (name "unconnected-(U2-CPFLT-Pad18)") (class "Default")
      (node (ref "U2") (pin "18") (pinfunction "CPFLT_18") (pintype "passive"))
    )
    (net (code "112") (name "unconnected-(U2-NC-Pad28)") (class "Default")
      (node (ref "U2") (pin "28") (pinfunction "NC_28") (pintype "passive"))
    )
    (net (code "113") (name "unconnected-(U2-NC_2-Pad8)") (class "Default")
      (node (ref "U2") (pin "8") (pinfunction "NC_2_8") (pintype "passive"))
    )
    (net (code "114") (name "unconnected-(U2-NC_3-Pad9)") (class "Default")
      (node (ref "U2") (pin "9") (pinfunction "NC_3_9") (pintype "passive"))
    )
    (net (code "115") (name "unconnected-(U2-NC_4-Pad17)") (class "Default")
      (node (ref "U2") (pin "17") (pinfunction "NC_4_17") (pintype "passive"))
    )
    (net (code "116") (name "unconnected-(U2-NC_5-Pad19)") (class "Default")
      (node (ref "U2") (pin "19") (pinfunction "NC_5_19") (pintype "passive"))
    )
    (net (code "117") (name "unconnected-(U2-NC_6-Pad22)") (class "Default")
      (node (ref "U2") (pin "22") (pinfunction "NC_6_22") (pintype "passive"))
    )
    (net (code "118") (name "unconnected-(U2-VDDD-Pad30)") (class "Default")
      (node (ref "U2") (pin "30") (pinfunction "VDDD_30") (pintype "power_in"))
    )
    (net (code "119") (name "unconnected-(U5-AIO1-Pad35)") (class "Default")
      (node (ref "U5") (pin "35") (pinfunction "AIO1_35") (pintype "bidirectional"))
    )
    (net (code "120") (name "unconnected-(U5-AIO2-Pad30)") (class "Default")
      (node (ref "U5") (pin "30") (pinfunction "AIO2_30") (pintype "bidirectional"))
    )
    (net (code "121") (name "unconnected-(U5-NC-Pad26)") (class "Default")
      (node (ref "U5") (pin "26") (pinfunction "NC_26") (pintype "bidirectional"))
    )
    (net (code "122") (name "unconnected-(U5-PCMCLK-Pad7)") (class "Default")
      (node (ref "U5") (pin "7") (pinfunction "PCMCLK_7") (pintype "bidirectional"))
    )
    (net (code "123") (name "unconnected-(U5-PCMIN-Pad9)") (class "Default")
      (node (ref "U5") (pin "9") (pinfunction "PCMIN_9") (pintype "bidirectional"))
    )
    (net (code "124") (name "unconnected-(U5-PCMOUT-Pad10)") (class "Default")
      (node (ref "U5") (pin "10") (pinfunction "PCMOUT_10") (pintype "bidirectional"))
    )
    (net (code "125") (name "unconnected-(U5-PCMSYNC-Pad8)") (class "Default")
      (node (ref "U5") (pin "8") (pinfunction "PCMSYNC_8") (pintype "bidirectional"))
    )
    (net (code "126") (name "unconnected-(U5-PIO3-Pad20)") (class "Default")
      (node (ref "U5") (pin "20") (pinfunction "PIO3_20") (pintype "bidirectional"))
    )
    (net (code "127") (name "unconnected-(U5-PIO6-Pad3)") (class "Default")
      (node (ref "U5") (pin "3") (pinfunction "PIO6_3") (pintype "bidirectional"))
    )
    (net (code "128") (name "unconnected-(U5-PIO7-Pad4)") (class "Default")
      (node (ref "U5") (pin "4") (pinfunction "PIO7_4") (pintype "bidirectional"))
    )
    (net (code "129") (name "unconnected-(U5-PIO8-Pad34)") (class "Default")
      (node (ref "U5") (pin "34") (pinfunction "PIO8_34") (pintype "bidirectional"))
    )
    (net (code "130") (name "unconnected-(U5-PIO9-Pad33)") (class "Default")
      (node (ref "U5") (pin "33") (pinfunction "PIO9_33") (pintype "bidirectional"))
    )
    (net (code "131") (name "unconnected-(U5-PIO10-Pad32)") (class "Default")
      (node (ref "U5") (pin "32") (pinfunction "PIO10_32") (pintype "bidirectional"))
    )
    (net (code "132") (name "unconnected-(U5-PIO11-Pad31)") (class "Default")
      (node (ref "U5") (pin "31") (pinfunction "PIO11_31") (pintype "bidirectional"))
    )
    (net (code "133") (name "unconnected-(U5-RESET-Pad5)") (class "Default")
      (node (ref "U5") (pin "5") (pinfunction "RESET_5") (pintype "bidirectional"))
    )
    (net (code "134") (name "unconnected-(U5-SPICLK-Pad6)") (class "Default")
      (node (ref "U5") (pin "6") (pinfunction "SPICLK_6") (pintype "bidirectional"))
    )
    (net (code "135") (name "unconnected-(U5-SPICSB-Pad23)") (class "Default")
      (node (ref "U5") (pin "23") (pinfunction "SPICSB_23") (pintype "bidirectional"))
    )
    (net (code "136") (name "unconnected-(U5-SPIMISO-Pad24)") (class "Default")
      (node (ref "U5") (pin "24") (pinfunction "SPIMISO_24") (pintype "bidirectional"))
    )
    (net (code "137") (name "unconnected-(U5-SPIMOSI-Pad2)") (class "Default")
      (node (ref "U5") (pin "2") (pinfunction "SPIMOSI_2") (pintype "bidirectional"))
    )
    (net (code "138") (name "unconnected-(U5-USBD+-Pad17)") (class "Default")
      (node (ref "U5") (pin "17") (pinfunction "USBD+_17") (pintype "bidirectional"))
    )
    (net (code "139") (name "unconnected-(U5-USBD--Pad18)") (class "Default")
      (node (ref "U5") (pin "18") (pinfunction "USBD-_18") (pintype "bidirectional"))
    )
  )
)
